# kembali_ke_awal.net
KiCad netlist of a schematic drawn in Altium Designer
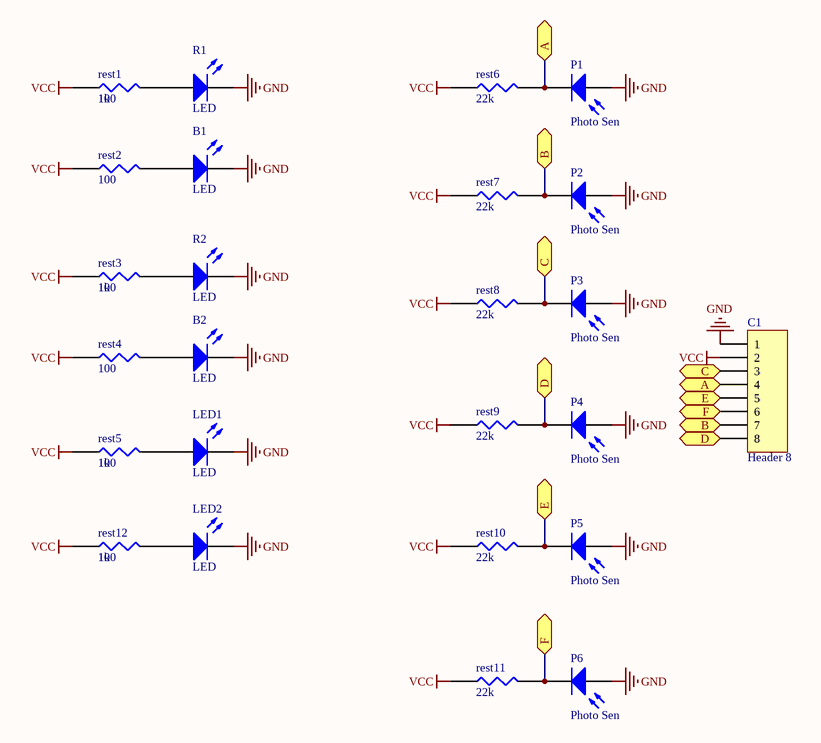
[diagram p0: kembali ke awal.SchDoc]

(export (version "E")
  (design (tool "Eeschema 10.0.6"))
  (components
    (comp (ref "B1")
      (value "LED")
      (footprint "My_LED3MM")
      (description "Typical INFRARED GaAs LED")
      (fields (field (name "PUBLISHER") "Altium Limited"))
      (libsource (lib "Mylib") (part "LED"))
    )
    (comp (ref "B2")
      (value "LED")
      (footprint "My_LED3MM")
      (description "Typical INFRARED GaAs LED")
      (fields (field (name "PUBLISHER") "Altium Limited"))
      (libsource (lib "Mylib") (part "LED"))
    )
    (comp (ref "C1")
      (value "Header 8")
      (footprint "HDR1X8")
      (description "Header, 8-Pin")
      (fields (field (name "PUBLISHER") "Altium Limited"))
      (libsource (lib "Miscellaneous Connectors") (part "Header 8"))
    )
    (comp (ref "LED1")
      (value "LED")
      (footprint "My_LED3MM")
      (description "Typical INFRARED GaAs LED")
      (fields (field (name "PUBLISHER") "Altium Limited"))
      (libsource (lib "Mylib") (part "LED"))
    )
    (comp (ref "LED2")
      (value "LED")
      (footprint "My_LED3MM")
      (description "Typical INFRARED GaAs LED")
      (fields (field (name "PUBLISHER") "Altium Limited"))
      (libsource (lib "Mylib") (part "LED"))
    )
    (comp (ref "P1")
      (value "Photo Sen")
      (footprint "PIN2")
      (description "Photosensitive Diode")
      (fields (field (name "PUBLISHER") "Altium Limited"))
      (libsource (lib "Miscellaneous Devices") (part "Photo Sen"))
    )
    (comp (ref "P2")
      (value "Photo Sen")
      (footprint "PIN2")
      (description "Photosensitive Diode")
      (fields (field (name "PUBLISHER") "Altium Limited"))
      (libsource (lib "Miscellaneous Devices") (part "Photo Sen"))
    )
    (comp (ref "P3")
      (value "Photo Sen")
      (footprint "PIN2")
      (description "Photosensitive Diode")
      (fields (field (name "PUBLISHER") "Altium Limited"))
      (libsource (lib "Miscellaneous Devices") (part "Photo Sen"))
    )
    (comp (ref "P4")
      (value "Photo Sen")
      (footprint "PIN2")
      (description "Photosensitive Diode")
      (fields (field (name "PUBLISHER") "Altium Limited"))
      (libsource (lib "Miscellaneous Devices") (part "Photo Sen"))
    )
    (comp (ref "P5")
      (value "Photo Sen")
      (footprint "PIN2")
      (description "Photosensitive Diode")
      (fields (field (name "PUBLISHER") "Altium Limited"))
      (libsource (lib "Miscellaneous Devices") (part "Photo Sen"))
    )
    (comp (ref "P6")
      (value "Photo Sen")
      (footprint "PIN2")
      (description "Photosensitive Diode")
      (fields (field (name "PUBLISHER") "Altium Limited"))
      (libsource (lib "Miscellaneous Devices") (part "Photo Sen"))
    )
    (comp (ref "R1")
      (value "LED")
      (footprint "My_LED3MM")
      (description "Typical INFRARED GaAs LED")
      (fields (field (name "PUBLISHER") "Altium Limited"))
      (libsource (lib "Mylib") (part "LED"))
    )
    (comp (ref "R2")
      (value "LED")
      (footprint "My_LED3MM")
      (description "Typical INFRARED GaAs LED")
      (fields (field (name "PUBLISHER") "Altium Limited"))
      (libsource (lib "Mylib") (part "LED"))
    )
    (comp (ref "rest1")
      (value "1k")
      (footprint "AXIAL-0.3")
      (description "resistor 1/4 wat")
      (fields (field (name "ALTIUM_VALUE") "100"))
      (libsource (lib "Mylib") (part "Res"))
    )
    (comp (ref "rest2")
      (value "100")
      (footprint "AXIAL-0.3")
      (description "resistor 1/4 wat")
      (libsource (lib "Mylib") (part "Res"))
    )
    (comp (ref "rest3")
      (value "1k")
      (footprint "AXIAL-0.3")
      (description "resistor 1/4 wat")
      (fields (field (name "ALTIUM_VALUE") "100"))
      (libsource (lib "Mylib") (part "Res"))
    )
    (comp (ref "rest4")
      (value "100")
      (footprint "AXIAL-0.3")
      (description "resistor 1/4 wat")
      (libsource (lib "Mylib") (part "Res"))
    )
    (comp (ref "rest5")
      (value "1k")
      (footprint "AXIAL-0.3")
      (description "resistor 1/4 wat")
      (fields (field (name "ALTIUM_VALUE") "100"))
      (libsource (lib "Mylib") (part "Res"))
    )
    (comp (ref "rest6")
      (value "22k")
      (footprint "AXIAL-0.3")
      (description "resistor 1/4 wat")
      (fields (field (name "Comment") "1k"))
      (libsource (lib "Mylib") (part "Res"))
    )
    (comp (ref "rest7")
      (value "22k")
      (footprint "AXIAL-0.3")
      (description "resistor 1/4 wat")
      (fields (field (name "Comment") "1k"))
      (libsource (lib "Mylib") (part "Res"))
    )
    (comp (ref "rest8")
      (value "22k")
      (footprint "AXIAL-0.3")
      (description "resistor 1/4 wat")
      (fields (field (name "Comment") "1k"))
      (libsource (lib "Mylib") (part "Res"))
    )
    (comp (ref "rest9")
      (value "22k")
      (footprint "AXIAL-0.3")
      (description "resistor 1/4 wat")
      (fields (field (name "Comment") "1k"))
      (libsource (lib "Mylib") (part "Res"))
    )
    (comp (ref "rest10")
      (value "22k")
      (footprint "AXIAL-0.3")
      (description "resistor 1/4 wat")
      (fields (field (name "Comment") "1k"))
      (libsource (lib "Mylib") (part "Res"))
    )
    (comp (ref "rest11")
      (value "22k")
      (footprint "AXIAL-0.3")
      (description "resistor 1/4 wat")
      (fields (field (name "Comment") "1k"))
      (libsource (lib "Mylib") (part "Res"))
    )
    (comp (ref "rest12")
      (value "1k")
      (footprint "AXIAL-0.3")
      (description "resistor 1/4 wat")
      (fields (field (name "ALTIUM_VALUE") "100"))
      (libsource (lib "Mylib") (part "Res"))
    )
  )
  (nets
    (net (code "1") (name "/A") (class "Default")
      (node (ref "C1") (pin "4") (pinfunction "4_4") (pintype "passive"))
      (node (ref "P1") (pin "2") (pinfunction "K_2") (pintype "passive"))
      (node (ref "rest6") (pin "2") (pinfunction "2_2") (pintype "passive"))
    )
    (net (code "2") (name "/B") (class "Default")
      (node (ref "C1") (pin "7") (pinfunction "7_7") (pintype "passive"))
      (node (ref "P2") (pin "2") (pinfunction "K_2") (pintype "passive"))
      (node (ref "rest7") (pin "2") (pinfunction "2_2") (pintype "passive"))
    )
    (net (code "3") (name "/C") (class "Default")
      (node (ref "C1") (pin "3") (pinfunction "3_3") (pintype "passive"))
      (node (ref "P3") (pin "2") (pinfunction "K_2") (pintype "passive"))
      (node (ref "rest8") (pin "2") (pinfunction "2_2") (pintype "passive"))
    )
    (net (code "4") (name "/D") (class "Default")
      (node (ref "C1") (pin "8") (pinfunction "8_8") (pintype "passive"))
      (node (ref "P4") (pin "2") (pinfunction "K_2") (pintype "passive"))
      (node (ref "rest9") (pin "2") (pinfunction "2_2") (pintype "passive"))
    )
    (net (code "5") (name "/E") (class "Default")
      (node (ref "C1") (pin "5") (pinfunction "5_5") (pintype "passive"))
      (node (ref "P5") (pin "2") (pinfunction "K_2") (pintype "passive"))
      (node (ref "rest10") (pin "2") (pinfunction "2_2") (pintype "passive"))
    )
    (net (code "6") (name "/F") (class "Default")
      (node (ref "C1") (pin "6") (pinfunction "6_6") (pintype "passive"))
      (node (ref "P6") (pin "2") (pinfunction "K_2") (pintype "passive"))
      (node (ref "rest11") (pin "2") (pinfunction "2_2") (pintype "passive"))
    )
    (net (code "7") (name "GND") (class "Default")
      (node (ref "B1") (pin "K") (pinfunction "K_K") (pintype "passive"))
      (node (ref "B2") (pin "K") (pinfunction "K_K") (pintype "passive"))
      (node (ref "C1") (pin "1") (pinfunction "1_1") (pintype "passive"))
      (node (ref "LED1") (pin "K") (pinfunction "K_K") (pintype "passive"))
      (node (ref "LED2") (pin "K") (pinfunction "K_K") (pintype "passive"))
      (node (ref "P1") (pin "1") (pinfunction "A_1") (pintype "passive"))
      (node (ref "P2") (pin "1") (pinfunction "A_1") (pintype "passive"))
      (node (ref "P3") (pin "1") (pinfunction "A_1") (pintype "passive"))
      (node (ref "P4") (pin "1") (pinfunction "A_1") (pintype "passive"))
      (node (ref "P5") (pin "1") (pinfunction "A_1") (pintype "passive"))
      (node (ref "P6") (pin "1") (pinfunction "A_1") (pintype "passive"))
      (node (ref "R1") (pin "K") (pinfunction "K_K") (pintype "passive"))
      (node (ref "R2") (pin "K") (pinfunction "K_K") (pintype "passive"))
    )
    (net (code "8") (name "Net-(B1-PadA)") (class "Default")
      (node (ref "B1") (pin "A") (pinfunction "A_A") (pintype "passive"))
      (node (ref "rest2") (pin "2") (pinfunction "2_2") (pintype "passive"))
    )
    (net (code "9") (name "Net-(B2-PadA)") (class "Default")
      (node (ref "B2") (pin "A") (pinfunction "A_A") (pintype "passive"))
      (node (ref "rest4") (pin "2") (pinfunction "2_2") (pintype "passive"))
    )
    (net (code "10") (name "Net-(LED1-PadA)") (class "Default")
      (node (ref "LED1") (pin "A") (pinfunction "A_A") (pintype "passive"))
      (node (ref "rest5") (pin "2") (pinfunction "2_2") (pintype "passive"))
    )
    (net (code "11") (name "Net-(LED2-PadA)") (class "Default")
      (node (ref "LED2") (pin "A") (pinfunction "A_A") (pintype "passive"))
      (node (ref "rest12") (pin "2") (pinfunction "2_2") (pintype "passive"))
    )
    (net (code "12") (name "Net-(R1-PadA)") (class "Default")
      (node (ref "R1") (pin "A") (pinfunction "A_A") (pintype "passive"))
      (node (ref "rest1") (pin "2") (pinfunction "2_2") (pintype "passive"))
    )
    (net (code "13") (name "Net-(R2-PadA)") (class "Default")
      (node (ref "R2") (pin "A") (pinfunction "A_A") (pintype "passive"))
      (node (ref "rest3") (pin "2") (pinfunction "2_2") (pintype "passive"))
    )
    (net (code "14") (name "VCC") (class "Default")
      (node (ref "C1") (pin "2") (pinfunction "2_2") (pintype "passive"))
      (node (ref "rest1") (pin "1") (pinfunction "1_1") (pintype "passive"))
      (node (ref "rest10") (pin "1") (pinfunction "1_1") (pintype "passive"))
      (node (ref "rest11") (pin "1") (pinfunction "1_1") (pintype "passive"))
      (node (ref "rest12") (pin "1") (pinfunction "1_1") (pintype "passive"))
      (node (ref "rest2") (pin "1") (pinfunction "1_1") (pintype "passive"))
      (node (ref "rest3") (pin "1") (pinfunction "1_1") (pintype "passive"))
      (node (ref "rest4") (pin "1") (pinfunction "1_1") (pintype "passive"))
      (node (ref "rest5") (pin "1") (pinfunction "1_1") (pintype "passive"))
      (node (ref "rest6") (pin "1") (pinfunction "1_1") (pintype "passive"))
      (node (ref "rest7") (pin "1") (pinfunction "1_1") (pintype "passive"))
      (node (ref "rest8") (pin "1") (pinfunction "1_1") (pintype "passive"))
      (node (ref "rest9") (pin "1") (pinfunction "1_1") (pintype "passive"))
    )
  )
)
